# Camera_Shield_Camera_SDCARD.net
KiCad netlist of a schematic drawn in Altium Designer
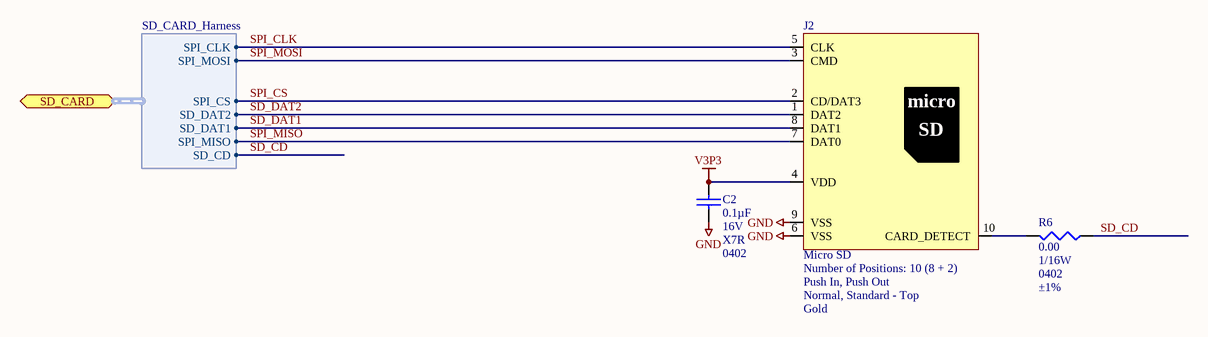
[diagram p0: Camera_Shield_Camera_SDCARD.SchDoc]

(export (version "E")
  (design (tool "Eeschema 10.0.6"))
  (components
    (comp (ref "C2")
      (value "C_0402_0.1UF_16V")
      (footprint "C_ERA-0402")
      (description "CAP CER .10UF 16V X7R 0402")
      (fields
        (field (name "MANUFACTURER") "TDK Corporation")
        (field (name "MANUFACTURER PART NUMBER") "C1005X7R1C104K")
        (field (name "CAPACITANCE") "0.1µF")
        (field (name "VOLTAGE - RATED") "16V")
        (field (name "TEMPERATURE COEFFICIENT") "X7R")
        (field (name "PACKAGE / CASE") "0402")
      )
      (libsource (lib "Main Library") (part "C_0402_0.1UF_16V"))
    )
    (comp (ref "J2")
      (value "Micro SD")
      (footprint "MICRO SD")
      (description "CONN MICRO SD R/A PUSH-PUSH SMD")
      (fields
        (field (name "MANUFACTURER") "Molex Inc")
        (field (name "MANUFACTURER PART NUMBER") "502570-0893")
        (field (name "NUMBER OF POSITIONS") "10 (8 + 2)")
        (field (name "INSERTION, REMOVAL METHOD") "Push In, Push Out")
        (field (name "MOUNTING FEATURE") "Normal, Standard - Top")
        (field (name "CONTACT FINISH") "Gold")
      )
      (libsource (lib "Main Library") (part "J_MICRO_SD"))
    )
    (comp (ref "R6")
      (value "R_0402_0.0")
      (footprint "ERA-0402")
      (description "RES 1.00 OHM 1/16W 1% 0402 SMD")
      (fields
        (field (name "MANUFACTURER") "Panasonic - ECG")
        (field (name "MANUFACTURER PART NUMBER") "ERJ-2GE0R00X")
        (field (name "RESISTANCE IN OHMS") "0.00")
        (field (name "POWER (WATTS)") "1/16W")
        (field (name "CASE") "0402")
        (field (name "TOLERANCE") "±1%")
      )
      (libsource (lib "Main Library") (part "R_0402_0.00"))
    )
  )
  (nets
    (net (code "2") (name "/SD_CD") (class "Default")
      (node (ref "R6") (pin "2") (pinfunction "2_2") (pintype "passive"))
    )
    (net (code "3") (name "/SD_DAT1") (class "Default")
      (node (ref "J2") (pin "8") (pinfunction "DAT1_8") (pintype "passive"))
    )
    (net (code "4") (name "/SD_DAT2") (class "Default")
      (node (ref "J2") (pin "1") (pinfunction "DAT2_1") (pintype "passive"))
    )
    (net (code "5") (name "/SPI_CLK") (class "Default")
      (node (ref "J2") (pin "5") (pinfunction "CLK_5") (pintype "passive"))
    )
    (net (code "6") (name "/SPI_CS") (class "Default")
      (node (ref "J2") (pin "2") (pinfunction "CD/DAT3_2") (pintype "passive"))
    )
    (net (code "7") (name "/SPI_MISO") (class "Default")
      (node (ref "J2") (pin "7") (pinfunction "DAT0_7") (pintype "passive"))
    )
    (net (code "8") (name "/SPI_MOSI") (class "Default")
      (node (ref "J2") (pin "3") (pinfunction "CMD_3") (pintype "passive"))
    )
    (net (code "10") (name "GND") (class "Default")
      (node (ref "C2") (pin "1") (pinfunction "1_1") (pintype "passive"))
      (node (ref "J2") (pin "6") (pinfunction "VSS_6") (pintype "passive"))
      (node (ref "J2") (pin "9") (pinfunction "VSS_9") (pintype "passive"))
    )
    (net (code "11") (name "Net-(J2-CARD_DETECT)") (class "Default")
      (node (ref "J2") (pin "10") (pinfunction "CARD_DETECT_10") (pintype "passive"))
      (node (ref "R6") (pin "1") (pinfunction "1_1") (pintype "passive"))
    )
    (net (code "12") (name "V3P3") (class "Default")
      (node (ref "C2") (pin "2") (pinfunction "2_2") (pintype "passive"))
      (node (ref "J2") (pin "4") (pinfunction "VDD_4") (pintype "passive"))
    )
  )
)
